# Detector.net
KiCad netlist of a schematic drawn in Altium Designer
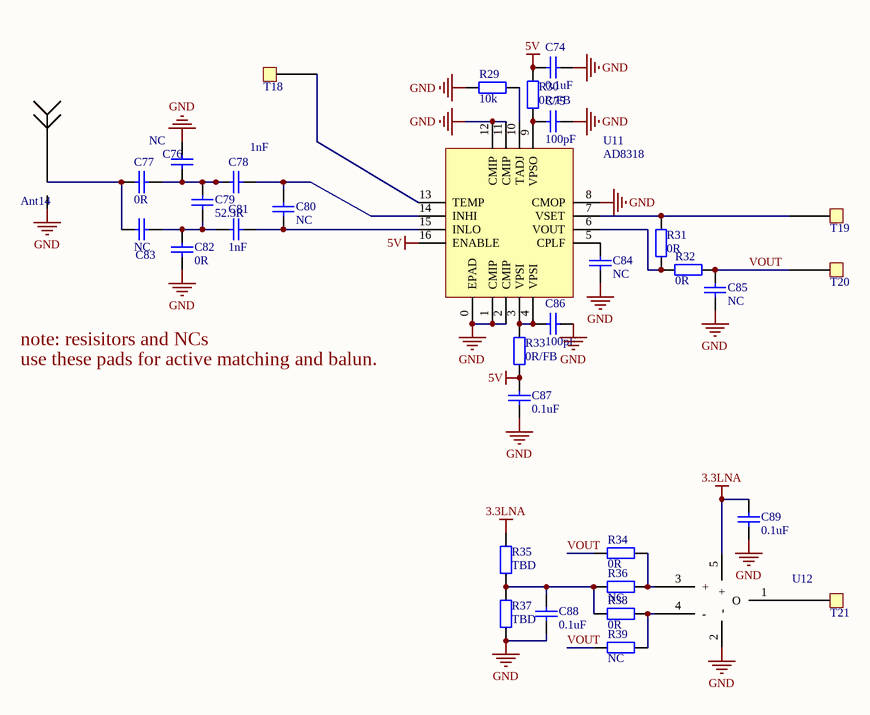
[diagram p0: Detector.SchDoc]

(export (version "E")
  (design (tool "Eeschema 10.0.6"))
  (components
    (comp (ref "Ant14") (value "Antenna") (footprint "SMA-2") (libsource (lib "F4SDR") (part "Antenna")))
    (comp (ref "C74")
      (value "0.1uF")
      (footprint "0402")
      (description "Capacitor")
      (fields (field (name "Comment") "Cap") (field (name "PUBLISHER") "Altium Limited"))
      (libsource (lib "RTC6705") (part "Cap"))
    )
    (comp (ref "C75")
      (value "100pF")
      (footprint "0402")
      (description "Capacitor")
      (fields (field (name "Comment") "Cap") (field (name "PUBLISHER") "Altium Limited"))
      (libsource (lib "RTC6705") (part "Cap"))
    )
    (comp (ref "C76")
      (value "NC")
      (footprint "0402")
      (description "Capacitor")
      (fields (field (name "Comment") "Cap") (field (name "PUBLISHER") "Altium Limited"))
      (libsource (lib "RTC6705") (part "Cap"))
    )
    (comp (ref "C77")
      (value "0R")
      (footprint "0402")
      (description "Capacitor")
      (fields (field (name "Comment") "Cap") (field (name "PUBLISHER") "Altium Limited"))
      (libsource (lib "RTC6705") (part "Cap"))
    )
    (comp (ref "C78")
      (value "1nF")
      (footprint "0402")
      (description "Capacitor")
      (fields (field (name "Comment") "Cap") (field (name "PUBLISHER") "Altium Limited"))
      (libsource (lib "RTC6705") (part "Cap"))
    )
    (comp (ref "C79")
      (value "52.3R")
      (footprint "0402")
      (description "Capacitor")
      (fields (field (name "Comment") "Cap") (field (name "PUBLISHER") "Altium Limited"))
      (libsource (lib "RTC6705") (part "Cap"))
    )
    (comp (ref "C80")
      (value "NC")
      (footprint "0402")
      (description "Capacitor")
      (fields (field (name "Comment") "Cap") (field (name "PUBLISHER") "Altium Limited"))
      (libsource (lib "RTC6705") (part "Cap"))
    )
    (comp (ref "C81")
      (value "1nF")
      (footprint "0402")
      (description "Capacitor")
      (fields (field (name "Comment") "Cap") (field (name "PUBLISHER") "Altium Limited"))
      (libsource (lib "RTC6705") (part "Cap"))
    )
    (comp (ref "C82")
      (value "0R")
      (footprint "0402")
      (description "Capacitor")
      (fields (field (name "Comment") "Cap") (field (name "PUBLISHER") "Altium Limited"))
      (libsource (lib "RTC6705") (part "Cap"))
    )
    (comp (ref "C83")
      (value "NC")
      (footprint "0402")
      (description "Capacitor")
      (fields (field (name "Comment") "Cap") (field (name "PUBLISHER") "Altium Limited"))
      (libsource (lib "RTC6705") (part "Cap"))
    )
    (comp (ref "C84")
      (value "NC")
      (footprint "0402")
      (description "Capacitor")
      (fields (field (name "Comment") "Cap") (field (name "PUBLISHER") "Altium Limited"))
      (libsource (lib "RTC6705") (part "Cap"))
    )
    (comp (ref "C85")
      (value "NC")
      (footprint "0402")
      (description "Capacitor")
      (fields (field (name "Comment") "Cap") (field (name "PUBLISHER") "Altium Limited"))
      (libsource (lib "RTC6705") (part "Cap"))
    )
    (comp (ref "C86")
      (value "100pF")
      (footprint "0402")
      (description "Capacitor")
      (fields (field (name "Comment") "Cap") (field (name "PUBLISHER") "Altium Limited"))
      (libsource (lib "RTC6705") (part "Cap"))
    )
    (comp (ref "C87")
      (value "0.1uF")
      (footprint "0402")
      (description "Capacitor")
      (fields (field (name "Comment") "Cap") (field (name "PUBLISHER") "Altium Limited"))
      (libsource (lib "RTC6705") (part "Cap"))
    )
    (comp (ref "C88")
      (value "0.1uF")
      (footprint "0402")
      (description "Capacitor")
      (fields (field (name "Comment") "Cap") (field (name "PUBLISHER") "Altium Limited"))
      (libsource (lib "RTC6705") (part "Cap"))
    )
    (comp (ref "C89")
      (value "0.1uF")
      (footprint "0402")
      (description "Capacitor")
      (fields (field (name "Comment") "Cap") (field (name "PUBLISHER") "Altium Limited"))
      (libsource (lib "RTC6705") (part "Cap"))
    )
    (comp (ref "R29")
      (value "10k")
      (footprint "0402")
      (description "Resistor")
      (fields (field (name "Comment") "Res2") (field (name "PUBLISHER") "Altium Limited"))
      (libsource (lib "") (part "Res2_2"))
    )
    (comp (ref "R30")
      (value "0R/FB")
      (footprint "0402")
      (description "Resistor")
      (fields (field (name "Comment") "Res2") (field (name "PUBLISHER") "Altium Limited"))
      (libsource (lib "") (part "Res2_3"))
    )
    (comp (ref "R31")
      (value "0R")
      (footprint "0402")
      (description "Resistor")
      (fields (field (name "Comment") "Res2") (field (name "PUBLISHER") "Altium Limited"))
      (libsource (lib "") (part "Res2_3"))
    )
    (comp (ref "R32")
      (value "0R")
      (footprint "0402")
      (description "Resistor")
      (fields (field (name "Comment") "Res2") (field (name "PUBLISHER") "Altium Limited"))
      (libsource (lib "") (part "Res2_2"))
    )
    (comp (ref "R33")
      (value "0R/FB")
      (footprint "0402")
      (description "Resistor")
      (fields (field (name "Comment") "Res2") (field (name "PUBLISHER") "Altium Limited"))
      (libsource (lib "") (part "Res2_3"))
    )
    (comp (ref "R34")
      (value "0R")
      (footprint "0402")
      (description "Resistor")
      (fields (field (name "Comment") "Res2") (field (name "PUBLISHER") "Altium Limited"))
      (libsource (lib "") (part "Res2_1"))
    )
    (comp (ref "R35")
      (value "TBD")
      (footprint "0402")
      (description "Resistor")
      (fields (field (name "Comment") "Res2") (field (name "PUBLISHER") "Altium Limited"))
      (libsource (lib "") (part "Res2_3"))
    )
    (comp (ref "R36")
      (value "NC")
      (footprint "0402")
      (description "Resistor")
      (fields (field (name "Comment") "Res2") (field (name "PUBLISHER") "Altium Limited"))
      (libsource (lib "") (part "Res2_1"))
    )
    (comp (ref "R37")
      (value "TBD")
      (footprint "0402")
      (description "Resistor")
      (fields (field (name "Comment") "Res2") (field (name "PUBLISHER") "Altium Limited"))
      (libsource (lib "RTC6705") (part "Res2"))
    )
    (comp (ref "R38")
      (value "0R")
      (footprint "0402")
      (description "Resistor")
      (fields (field (name "Comment") "Res2") (field (name "PUBLISHER") "Altium Limited"))
      (libsource (lib "") (part "Res2_1"))
    )
    (comp (ref "R39")
      (value "NC")
      (footprint "0402")
      (description "Resistor")
      (fields (field (name "Comment") "Res2") (field (name "PUBLISHER") "Altium Limited"))
      (libsource (lib "") (part "Res2_1"))
    )
    (comp (ref "T18") (value "TestPad") (footprint "TestPad - 1mm") (libsource (lib "sch") (part "TestPad")))
    (comp (ref "T19") (value "TestPad") (footprint "TestPad - 1mm") (libsource (lib "") (part "TestPad_1")))
    (comp (ref "T20") (value "TestPad") (footprint "TestPad - 1mm") (libsource (lib "") (part "TestPad_1")))
    (comp (ref "T21") (value "TestPad") (footprint "TestPad - 1mm") (libsource (lib "") (part "TestPad_1")))
    (comp (ref "U11") (value "AD8318") (footprint "AD8318") (libsource (lib "F4SDR") (part "AD8318")))
    (comp (ref "U12") (value "CMP-SOT23") (footprint "SOT23-5") (libsource (lib "sch") (part "CMP-SOT23")))
  )
  (nets
    (net (code "1") (name "/VOUT") (class "Default")
      (node (ref "C85") (pin "1") (pinfunction "1_1") (pintype "passive"))
      (node (ref "R32") (pin "2") (pinfunction "2_2") (pintype "passive"))
      (node (ref "R34") (pin "2") (pinfunction "2_2") (pintype "passive"))
      (node (ref "R39") (pin "2") (pinfunction "2_2") (pintype "passive"))
      (node (ref "T20") (pin "1") (pinfunction "3_1") (pintype "passive"))
    )
    (net (code "2") (name "3.3LNA") (class "Default")
      (node (ref "C89") (pin "2") (pinfunction "2_2") (pintype "passive"))
      (node (ref "R35") (pin "1") (pinfunction "1_1") (pintype "passive"))
      (node (ref "U12") (pin "5") (pinfunction "+_5") (pintype "passive"))
    )
    (net (code "3") (name "5V") (class "Default")
      (node (ref "C74") (pin "2") (pinfunction "2_2") (pintype "passive"))
      (node (ref "C87") (pin "2") (pinfunction "2_2") (pintype "passive"))
      (node (ref "R30") (pin "1") (pinfunction "1_1") (pintype "passive"))
      (node (ref "R33") (pin "2") (pinfunction "2_2") (pintype "passive"))
      (node (ref "U11") (pin "16") (pinfunction "ENABLE_16") (pintype "passive"))
    )
    (net (code "4") (name "GND") (class "Default")
      (node (ref "Ant14") (pin "GND") (pinfunction "G_GND") (pintype "passive"))
      (node (ref "C74") (pin "1") (pinfunction "1_1") (pintype "passive"))
      (node (ref "C75") (pin "1") (pinfunction "1_1") (pintype "passive"))
      (node (ref "C76") (pin "1") (pinfunction "1_1") (pintype "passive"))
      (node (ref "C82") (pin "1") (pinfunction "1_1") (pintype "passive"))
      (node (ref "C84") (pin "2") (pinfunction "2_2") (pintype "passive"))
      (node (ref "C85") (pin "2") (pinfunction "2_2") (pintype "passive"))
      (node (ref "C86") (pin "1") (pinfunction "1_1") (pintype "passive"))
      (node (ref "C87") (pin "1") (pinfunction "1_1") (pintype "passive"))
      (node (ref "C88") (pin "2") (pinfunction "2_2") (pintype "passive"))
      (node (ref "C89") (pin "1") (pinfunction "1_1") (pintype "passive"))
      (node (ref "R29") (pin "1") (pinfunction "1_1") (pintype "passive"))
      (node (ref "R37") (pin "1") (pinfunction "1_1") (pintype "passive"))
      (node (ref "U11") (pin "0") (pinfunction "EPAD_0") (pintype "passive"))
      (node (ref "U11") (pin "1") (pinfunction "CMIP_1") (pintype "passive"))
      (node (ref "U11") (pin "11") (pinfunction "CMIP_11") (pintype "passive"))
      (node (ref "U11") (pin "12") (pinfunction "CMIP_12") (pintype "passive"))
      (node (ref "U11") (pin "2") (pinfunction "CMIP_2") (pintype "passive"))
      (node (ref "U11") (pin "8") (pinfunction "CMOP_8") (pintype "passive"))
      (node (ref "U12") (pin "2") (pinfunction "-_2") (pintype "passive"))
    )
    (net (code "5") (name "Net-(Ant14-Pad1)") (class "Default")
      (node (ref "Ant14") (pin "1") (pinfunction "1_1") (pintype "passive"))
      (node (ref "C77") (pin "2") (pinfunction "2_2") (pintype "passive"))
      (node (ref "C83") (pin "2") (pinfunction "2_2") (pintype "passive"))
    )
    (net (code "6") (name "Net-(C76-Pad2)") (class "Default")
      (node (ref "C76") (pin "2") (pinfunction "2_2") (pintype "passive"))
      (node (ref "C77") (pin "1") (pinfunction "1_1") (pintype "passive"))
      (node (ref "C78") (pin "2") (pinfunction "2_2") (pintype "passive"))
      (node (ref "C79") (pin "2") (pinfunction "2_2") (pintype "passive"))
    )
    (net (code "7") (name "Net-(C79-Pad1)") (class "Default")
      (node (ref "C79") (pin "1") (pinfunction "1_1") (pintype "passive"))
      (node (ref "C81") (pin "2") (pinfunction "2_2") (pintype "passive"))
      (node (ref "C82") (pin "2") (pinfunction "2_2") (pintype "passive"))
      (node (ref "C83") (pin "1") (pinfunction "1_1") (pintype "passive"))
    )
    (net (code "8") (name "Net-(C86-Pad2)") (class "Default")
      (node (ref "C86") (pin "2") (pinfunction "2_2") (pintype "passive"))
      (node (ref "R33") (pin "1") (pinfunction "1_1") (pintype "passive"))
      (node (ref "U11") (pin "3") (pinfunction "VPSI_3") (pintype "passive"))
      (node (ref "U11") (pin "4") (pinfunction "VPSI_4") (pintype "passive"))
    )
    (net (code "9") (name "Net-(C88-Pad1)") (class "Default")
      (node (ref "C88") (pin "1") (pinfunction "1_1") (pintype "passive"))
      (node (ref "R35") (pin "2") (pinfunction "2_2") (pintype "passive"))
      (node (ref "R36") (pin "2") (pinfunction "2_2") (pintype "passive"))
      (node (ref "R37") (pin "2") (pinfunction "2_2") (pintype "passive"))
      (node (ref "R38") (pin "2") (pinfunction "2_2") (pintype "passive"))
    )
    (net (code "10") (name "Net-(R34-Pad1)") (class "Default")
      (node (ref "R34") (pin "1") (pinfunction "1_1") (pintype "passive"))
      (node (ref "R36") (pin "1") (pinfunction "1_1") (pintype "passive"))
      (node (ref "U12") (pin "3") (pinfunction "+_3") (pintype "passive"))
    )
    (net (code "11") (name "Net-(R38-Pad1)") (class "Default")
      (node (ref "R38") (pin "1") (pinfunction "1_1") (pintype "passive"))
      (node (ref "R39") (pin "1") (pinfunction "1_1") (pintype "passive"))
      (node (ref "U12") (pin "4") (pinfunction "-_4") (pintype "passive"))
    )
    (net (code "12") (name "Net-(T18-3)") (class "Default")
      (node (ref "T18") (pin "1") (pinfunction "3_1") (pintype "passive"))
      (node (ref "U11") (pin "13") (pinfunction "TEMP_13") (pintype "passive"))
    )
    (net (code "13") (name "Net-(T19-3)") (class "Default")
      (node (ref "R31") (pin "1") (pinfunction "1_1") (pintype "passive"))
      (node (ref "T19") (pin "1") (pinfunction "3_1") (pintype "passive"))
      (node (ref "U11") (pin "7") (pinfunction "VSET_7") (pintype "passive"))
    )
    (net (code "14") (name "Net-(T21-3)") (class "Default")
      (node (ref "T21") (pin "1") (pinfunction "3_1") (pintype "passive"))
      (node (ref "U12") (pin "1") (pinfunction "O_1") (pintype "passive"))
    )
    (net (code "15") (name "Net-(U11-CPLF)") (class "Default")
      (node (ref "C84") (pin "1") (pinfunction "1_1") (pintype "passive"))
      (node (ref "U11") (pin "5") (pinfunction "CPLF_5") (pintype "passive"))
    )
    (net (code "16") (name "Net-(U11-INHI)") (class "Default")
      (node (ref "C78") (pin "1") (pinfunction "1_1") (pintype "passive"))
      (node (ref "C80") (pin "2") (pinfunction "2_2") (pintype "passive"))
      (node (ref "U11") (pin "14") (pinfunction "INHI_14") (pintype "passive"))
    )
    (net (code "17") (name "Net-(U11-INLO)") (class "Default")
      (node (ref "C80") (pin "1") (pinfunction "1_1") (pintype "passive"))
      (node (ref "C81") (pin "1") (pinfunction "1_1") (pintype "passive"))
      (node (ref "U11") (pin "15") (pinfunction "INLO_15") (pintype "passive"))
    )
    (net (code "18") (name "Net-(U11-TADJ)") (class "Default")
      (node (ref "R29") (pin "2") (pinfunction "2_2") (pintype "passive"))
      (node (ref "U11") (pin "10") (pinfunction "TADJ_10") (pintype "passive"))
    )
    (net (code "19") (name "Net-(U11-VOUT)") (class "Default")
      (node (ref "R31") (pin "2") (pinfunction "2_2") (pintype "passive"))
      (node (ref "R32") (pin "1") (pinfunction "1_1") (pintype "passive"))
      (node (ref "U11") (pin "6") (pinfunction "VOUT_6") (pintype "passive"))
    )
    (net (code "20") (name "Net-(U11-VPSO)") (class "Default")
      (node (ref "C75") (pin "2") (pinfunction "2_2") (pintype "passive"))
      (node (ref "R30") (pin "2") (pinfunction "2_2") (pintype "passive"))
      (node (ref "U11") (pin "9") (pinfunction "VPSO_9") (pintype "passive"))
    )
  )
)
